# RS485.net
KiCad netlist of a schematic drawn in Altium Designer
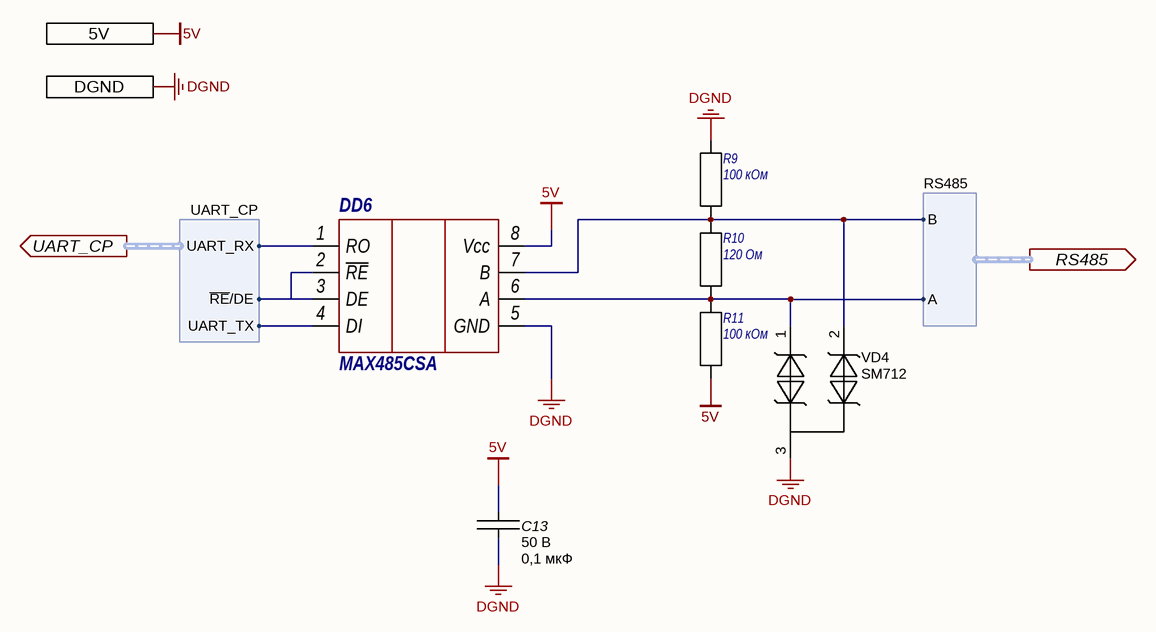
[diagram p0: RS485.SchDoc]

(export (version "E")
  (design (tool "Eeschema 10.0.6"))
  (components
    (comp (ref "C13")
      (value "0,1 мкФ")
      (footprint "C0603C")
      (description "SMD 0603 ; X7R; 0,1 мкФ; 50 В")
      (fields
        (field (name "PART NUMBER") "CC0603KRX7R9BB104")
        (field (name "MANUFACTURER") "YAGEO")
        (field (name "VOLTAGE") "50 В")
      )
      (libsource (lib "Capacitors") (part "CC0603KRX7R9BB104"))
    )
    (comp (ref "DD6")
      (value "MAX485CSA")
      (footprint "SOIC-8")
      (description "RS-485 приёмопередатчик")
      (libsource (lib "Hydrolib") (part "MAX485CSA"))
    )
    (comp (ref "R9")
      (value "100 кОм")
      (footprint "C0603R")
      (description "SMD 0603; 0,1; 1%; 100 кОм")
      (fields (field (name "PART NUMBER") "RC0603FR-07100KL") (field (name "POWER") "0,1"))
      (libsource (lib "Resistors") (part "RC0603FR-07100KL"))
    )
    (comp (ref "R10")
      (value "120 Ом")
      (footprint "C0603R")
      (description "SMD 0603; 0,1; 1%; 120 Ом")
      (fields (field (name "PART NUMBER") "RC0603FR-07120RL") (field (name "POWER") "0,1"))
      (libsource (lib "Resistors") (part "RC0603FR-07120RL"))
    )
    (comp (ref "R11")
      (value "100 кОм")
      (footprint "C0603R")
      (description "SMD 0603; 0,1; 1%; 100 кОм")
      (fields (field (name "PART NUMBER") "RC0603FR-07100KL") (field (name "POWER") "0,1"))
      (libsource (lib "Resistors") (part "RC0603FR-07100KL"))
    )
    (comp (ref "VD4")
      (value "SM712")
      (footprint "SOT23-3")
      (description "TVS RS485")
      (fields (field (name "MANUFACTURER") "Semtech") (field (name "PART NUMBER") "SM712.TCT"))
      (libsource (lib "VD") (part "SM712.TCT"))
    )
  )
  (nets
    (net (code "3") (name "/A") (class "Default")
      (node (ref "DD6") (pin "6") (pinfunction "A_6") (pintype "passive"))
      (node (ref "R10") (pin "2") (pinfunction "2_2") (pintype "passive"))
      (node (ref "R11") (pin "1") (pinfunction "1_1") (pintype "passive"))
      (node (ref "VD4") (pin "1") (pinfunction "1_1") (pintype "passive"))
    )
    (net (code "4") (name "/B") (class "Default")
      (node (ref "DD6") (pin "7") (pinfunction "B_7") (pintype "passive"))
      (node (ref "R10") (pin "1") (pinfunction "1_1") (pintype "passive"))
      (node (ref "R9") (pin "2") (pinfunction "2_2") (pintype "passive"))
      (node (ref "VD4") (pin "2") (pinfunction "2_2") (pintype "passive"))
    )
    (net (code "5") (name "/UART_RX") (class "Default")
      (node (ref "DD6") (pin "1") (pinfunction "RO_1") (pintype "passive"))
    )
    (net (code "6") (name "/UART_TX") (class "Default")
      (node (ref "DD6") (pin "4") (pinfunction "DI_4") (pintype "passive"))
    )
    (net (code "9") (name "/~{RE}{slash}DE") (class "Default")
      (node (ref "DD6") (pin "2") (pinfunction "RE_2") (pintype "passive"))
      (node (ref "DD6") (pin "3") (pinfunction "DE_3") (pintype "passive"))
    )
    (net (code "10") (name "5V") (class "Default")
      (node (ref "C13") (pin "1") (pinfunction "1_1") (pintype "passive"))
      (node (ref "DD6") (pin "8") (pinfunction "Vcc_8") (pintype "passive"))
      (node (ref "R11") (pin "2") (pinfunction "2_2") (pintype "passive"))
    )
    (net (code "11") (name "DGND") (class "Default")
      (node (ref "C13") (pin "2") (pinfunction "2_2") (pintype "passive"))
      (node (ref "DD6") (pin "5") (pinfunction "GND_5") (pintype "passive"))
      (node (ref "R9") (pin "1") (pinfunction "1_1") (pintype "passive"))
      (node (ref "VD4") (pin "3") (pinfunction "3_3") (pintype "passive"))
    )
  )
)
